# 5V_LINEAR_REGULATOR_BREAKOUT_V00.net
KiCad netlist of a schematic drawn in EAGLE
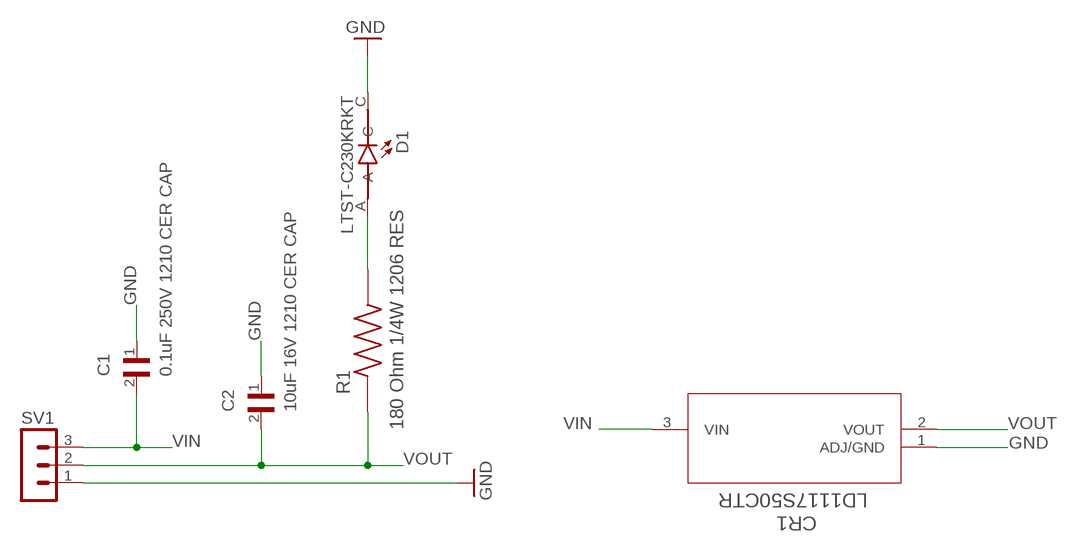
[diagram p0: schematic, sheet 1]

(export (version "E")
  (design (tool "Eeschema 10.0.6"))
  (components
    (comp (ref "C1")
      (value "0.1uF 250V 1210 CER CAP")
      (footprint "eagle-import:CAPC3225X280")
      (fields
        (field (name "DIGI-KEY_PART_NUMBER") "399-1267-1-ND")
        (field (name "MF") "KEMET")
        (field (name "MP") "C1210C104K5RACTU")
      )
      (libsource (lib "eagle-import") (part "C1210C104K5RACTU"))
    )
    (comp (ref "C2")
      (value "10uF 16V 1210 CER CAP")
      (footprint "eagle-import:CAPC3225X280")
      (fields
        (field (name "DIGI-KEY_PART_NUMBER") "399-1267-1-ND")
        (field (name "MF") "KEMET")
        (field (name "MP") "C1210C104K5RACTU")
      )
      (libsource (lib "eagle-import") (part "C1210C104K5RACTU"))
    )
    (comp (ref "CR1")
      (value "LD1117S50CTR")
      (footprint "eagle-import:SOT-223_STM")
      (libsource (lib "eagle-import") (part "LD1117S50CTR"))
    )
    (comp (ref "D1")
      (value "LTST-C230KRKT")
      (footprint "eagle-import:LEDC3216X110")
      (fields (field (name "DIGI-KEY_PART_NUMBER") "160-1457-1-ND") (field (name "MF") "Lite-On Inc."))
      (libsource (lib "eagle-import") (part "LTST-C230KRKT"))
    )
    (comp (ref "R1")
      (value "180 Ohm 1/4W 1206 RES")
      (footprint "eagle-import:RESC3116X65N")
      (fields
        (field (name "DIGI-KEY_PART_NUMBER") "311-10KERCT-ND")
        (field (name "MF") "Yageo")
        (field (name "MP") "RC1206JR-0710KL")
      )
      (libsource (lib "eagle-import") (part "RC1206JR-0710KL"))
    )
    (comp (ref "SV1")
      (value "MA03-1")
      (footprint "eagle-import:MA03-1")
      (libsource (lib "eagle-import") (part "MA03-1"))
    )
  )
  (nets
    (net (code "1") (name "/VIN") (class "Default")
      (node (ref "C1") (pin "2") (pinfunction "2_2") (pintype "passive"))
      (node (ref "CR1") (pin "3") (pinfunction "VIN_3") (pintype "power_in"))
      (node (ref "SV1") (pin "3") (pinfunction "3_3") (pintype "passive"))
    )
    (net (code "2") (name "/VOUT") (class "Default")
      (node (ref "C2") (pin "2") (pinfunction "2_2") (pintype "passive"))
      (node (ref "CR1") (pin "2") (pinfunction "VOUT_2") (pintype "power_in"))
      (node (ref "R1") (pin "1") (pinfunction "1_1") (pintype "passive"))
      (node (ref "SV1") (pin "2") (pinfunction "2_2") (pintype "passive"))
    )
    (net (code "3") (name "GND") (class "Default")
      (node (ref "C1") (pin "1") (pinfunction "1_1") (pintype "passive"))
      (node (ref "C2") (pin "1") (pinfunction "1_1") (pintype "passive"))
      (node (ref "CR1") (pin "1") (pinfunction "ADJ/GND_1") (pintype "passive"))
      (node (ref "D1") (pin "C") (pinfunction "C_C") (pintype "passive"))
      (node (ref "SV1") (pin "1") (pinfunction "1_1") (pintype "passive"))
    )
    (net (code "4") (name "Net-(D1-PadA)") (class "Default")
      (node (ref "D1") (pin "A") (pinfunction "A_A") (pintype "passive"))
      (node (ref "R1") (pin "2") (pinfunction "2_2") (pintype "passive"))
    )
  )
)
